# COMS0010_Comms_Test_Board.net
KiCad netlist of a schematic drawn in Altium Designer
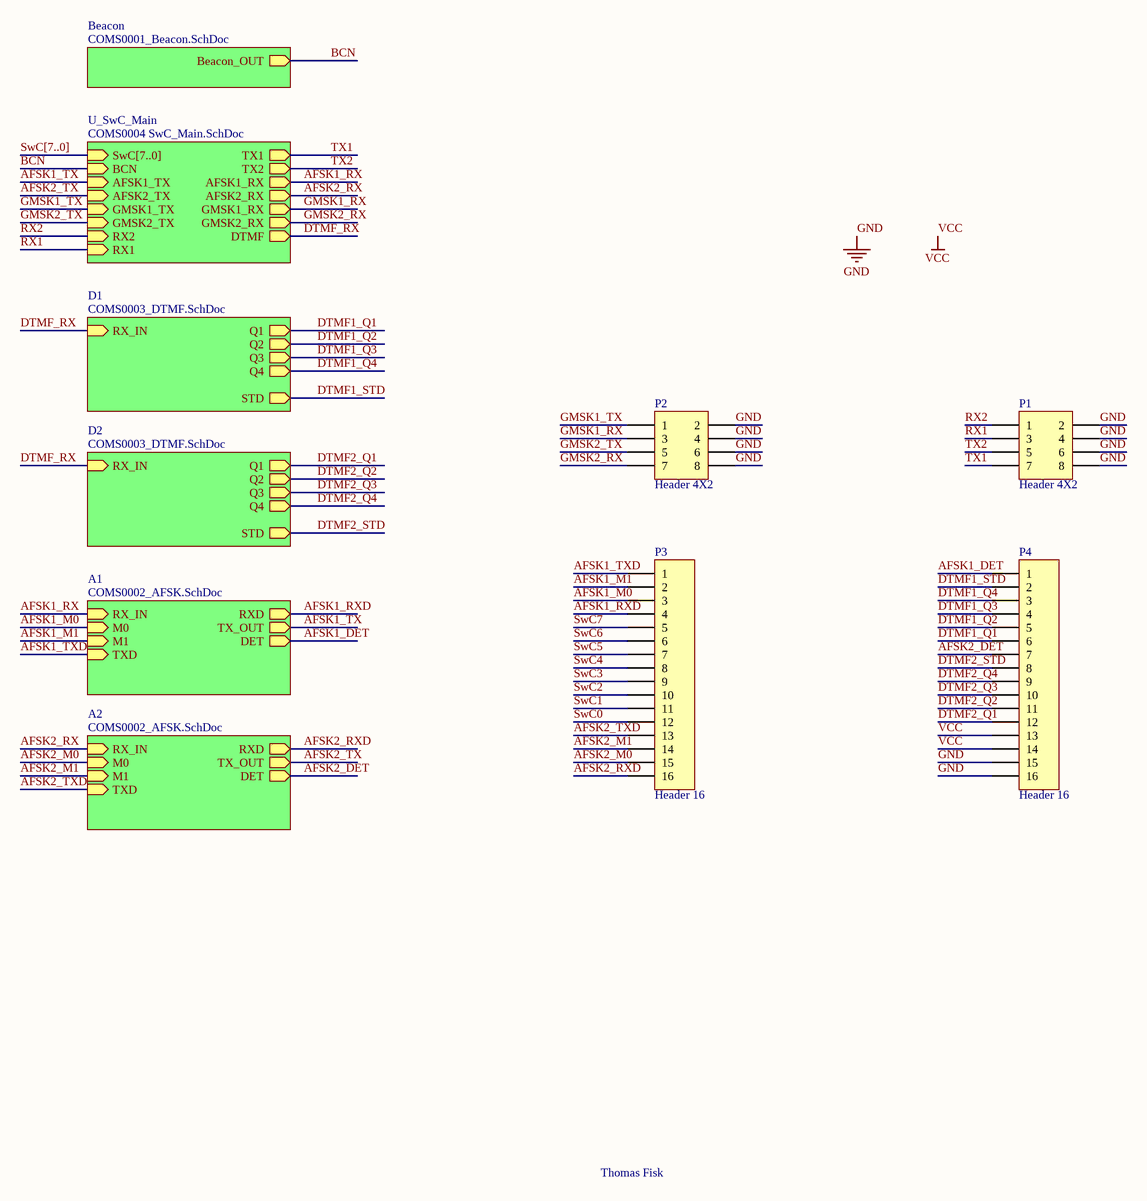
[diagram p0: COMS0010_Comms_Test_Board.SchDoc]

(export (version "E")
  (design (tool "Eeschema 10.0.6"))
  (components
    (comp (ref "P1")
      (value "Header 4X2")
      (footprint "HDR2X4")
      (description "Header, 4-Pin, Dual row")
      (fields (field (name "PUBLISHER") "Altium Limited"))
      (libsource (lib "Miscellaneous Connectors") (part "Header 4X2"))
    )
    (comp (ref "P2")
      (value "Header 4X2")
      (footprint "HDR2X4")
      (description "Header, 4-Pin, Dual row")
      (fields (field (name "PUBLISHER") "Altium Limited"))
      (libsource (lib "Miscellaneous Connectors") (part "Header 4X2"))
    )
    (comp (ref "P3")
      (value "Header 16")
      (footprint "HDR1X16")
      (description "Header, 16-Pin")
      (fields (field (name "PUBLISHER") "Altium Limited"))
      (libsource (lib "Miscellaneous Connectors") (part "Header 16"))
    )
    (comp (ref "P4")
      (value "Header 16")
      (footprint "HDR1X16")
      (description "Header, 16-Pin")
      (fields (field (name "PUBLISHER") "Altium Limited"))
      (libsource (lib "Miscellaneous Connectors") (part "Header 16"))
    )
  )
  (nets
    (net (code "1") (name "/AFSK1_DET") (class "Default")
      (node (ref "P4") (pin "1") (pinfunction "1_1") (pintype "passive"))
    )
    (net (code "2") (name "/AFSK1_M0") (class "Default")
      (node (ref "P3") (pin "3") (pinfunction "3_3") (pintype "passive"))
    )
    (net (code "3") (name "/AFSK1_M1") (class "Default")
      (node (ref "P3") (pin "2") (pinfunction "2_2") (pintype "passive"))
    )
    (net (code "5") (name "/AFSK1_RXD") (class "Default")
      (node (ref "P3") (pin "4") (pinfunction "4_4") (pintype "passive"))
    )
    (net (code "7") (name "/AFSK1_TXD") (class "Default")
      (node (ref "P3") (pin "1") (pinfunction "1_1") (pintype "passive"))
    )
    (net (code "8") (name "/AFSK2_DET") (class "Default")
      (node (ref "P4") (pin "7") (pinfunction "7_7") (pintype "passive"))
    )
    (net (code "9") (name "/AFSK2_M0") (class "Default")
      (node (ref "P3") (pin "15") (pinfunction "15_15") (pintype "passive"))
    )
    (net (code "10") (name "/AFSK2_M1") (class "Default")
      (node (ref "P3") (pin "14") (pinfunction "14_14") (pintype "passive"))
    )
    (net (code "12") (name "/AFSK2_RXD") (class "Default")
      (node (ref "P3") (pin "16") (pinfunction "16_16") (pintype "passive"))
    )
    (net (code "14") (name "/AFSK2_TXD") (class "Default")
      (node (ref "P3") (pin "13") (pinfunction "13_13") (pintype "passive"))
    )
    (net (code "16") (name "/DTMF1_Q1") (class "Default")
      (node (ref "P4") (pin "6") (pinfunction "6_6") (pintype "passive"))
    )
    (net (code "17") (name "/DTMF1_Q2") (class "Default")
      (node (ref "P4") (pin "5") (pinfunction "5_5") (pintype "passive"))
    )
    (net (code "18") (name "/DTMF1_Q3") (class "Default")
      (node (ref "P4") (pin "4") (pinfunction "4_4") (pintype "passive"))
    )
    (net (code "19") (name "/DTMF1_Q4") (class "Default")
      (node (ref "P4") (pin "3") (pinfunction "3_3") (pintype "passive"))
    )
    (net (code "20") (name "/DTMF1_STD") (class "Default")
      (node (ref "P4") (pin "2") (pinfunction "2_2") (pintype "passive"))
    )
    (net (code "21") (name "/DTMF2_Q1") (class "Default")
      (node (ref "P4") (pin "12") (pinfunction "12_12") (pintype "passive"))
    )
    (net (code "22") (name "/DTMF2_Q2") (class "Default")
      (node (ref "P4") (pin "11") (pinfunction "11_11") (pintype "passive"))
    )
    (net (code "23") (name "/DTMF2_Q3") (class "Default")
      (node (ref "P4") (pin "10") (pinfunction "10_10") (pintype "passive"))
    )
    (net (code "24") (name "/DTMF2_Q4") (class "Default")
      (node (ref "P4") (pin "9") (pinfunction "9_9") (pintype "passive"))
    )
    (net (code "25") (name "/DTMF2_STD") (class "Default")
      (node (ref "P4") (pin "8") (pinfunction "8_8") (pintype "passive"))
    )
    (net (code "27") (name "/GMSK1_RX") (class "Default")
      (node (ref "P2") (pin "3") (pinfunction "3_3") (pintype "passive"))
    )
    (net (code "28") (name "/GMSK1_TX") (class "Default")
      (node (ref "P2") (pin "1") (pinfunction "1_1") (pintype "passive"))
    )
    (net (code "29") (name "/GMSK2_RX") (class "Default")
      (node (ref "P2") (pin "7") (pinfunction "7_7") (pintype "passive"))
    )
    (net (code "30") (name "/GMSK2_TX") (class "Default")
      (node (ref "P2") (pin "5") (pinfunction "5_5") (pintype "passive"))
    )
    (net (code "31") (name "/RX1") (class "Default")
      (node (ref "P1") (pin "3") (pinfunction "3_3") (pintype "passive"))
    )
    (net (code "32") (name "/RX2") (class "Default")
      (node (ref "P1") (pin "1") (pinfunction "1_1") (pintype "passive"))
    )
    (net (code "33") (name "/SwC0") (class "Default")
      (node (ref "P3") (pin "12") (pinfunction "12_12") (pintype "passive"))
    )
    (net (code "34") (name "/SwC1") (class "Default")
      (node (ref "P3") (pin "11") (pinfunction "11_11") (pintype "passive"))
    )
    (net (code "35") (name "/SwC2") (class "Default")
      (node (ref "P3") (pin "10") (pinfunction "10_10") (pintype "passive"))
    )
    (net (code "36") (name "/SwC3") (class "Default")
      (node (ref "P3") (pin "9") (pinfunction "9_9") (pintype "passive"))
    )
    (net (code "37") (name "/SwC4") (class "Default")
      (node (ref "P3") (pin "8") (pinfunction "8_8") (pintype "passive"))
    )
    (net (code "38") (name "/SwC5") (class "Default")
      (node (ref "P3") (pin "7") (pinfunction "7_7") (pintype "passive"))
    )
    (net (code "39") (name "/SwC6") (class "Default")
      (node (ref "P3") (pin "6") (pinfunction "6_6") (pintype "passive"))
    )
    (net (code "40") (name "/SwC7") (class "Default")
      (node (ref "P3") (pin "5") (pinfunction "5_5") (pintype "passive"))
    )
    (net (code "42") (name "/TX1") (class "Default")
      (node (ref "P1") (pin "7") (pinfunction "7_7") (pintype "passive"))
    )
    (net (code "43") (name "/TX2") (class "Default")
      (node (ref "P1") (pin "5") (pinfunction "5_5") (pintype "passive"))
    )
    (net (code "44") (name "GND") (class "Default")
      (node (ref "P1") (pin "2") (pinfunction "2_2") (pintype "passive"))
      (node (ref "P1") (pin "4") (pinfunction "4_4") (pintype "passive"))
      (node (ref "P1") (pin "6") (pinfunction "6_6") (pintype "passive"))
      (node (ref "P1") (pin "8") (pinfunction "8_8") (pintype "passive"))
      (node (ref "P2") (pin "2") (pinfunction "2_2") (pintype "passive"))
      (node (ref "P2") (pin "4") (pinfunction "4_4") (pintype "passive"))
      (node (ref "P2") (pin "6") (pinfunction "6_6") (pintype "passive"))
      (node (ref "P2") (pin "8") (pinfunction "8_8") (pintype "passive"))
      (node (ref "P4") (pin "15") (pinfunction "15_15") (pintype "passive"))
      (node (ref "P4") (pin "16") (pinfunction "16_16") (pintype "passive"))
    )
    (net (code "45") (name "VCC") (class "Default")
      (node (ref "P4") (pin "13") (pinfunction "13_13") (pintype "passive"))
      (node (ref "P4") (pin "14") (pinfunction "14_14") (pintype "passive"))
    )
  )
)
